# BigClock.net
KiCad netlist of a schematic drawn in EAGLE
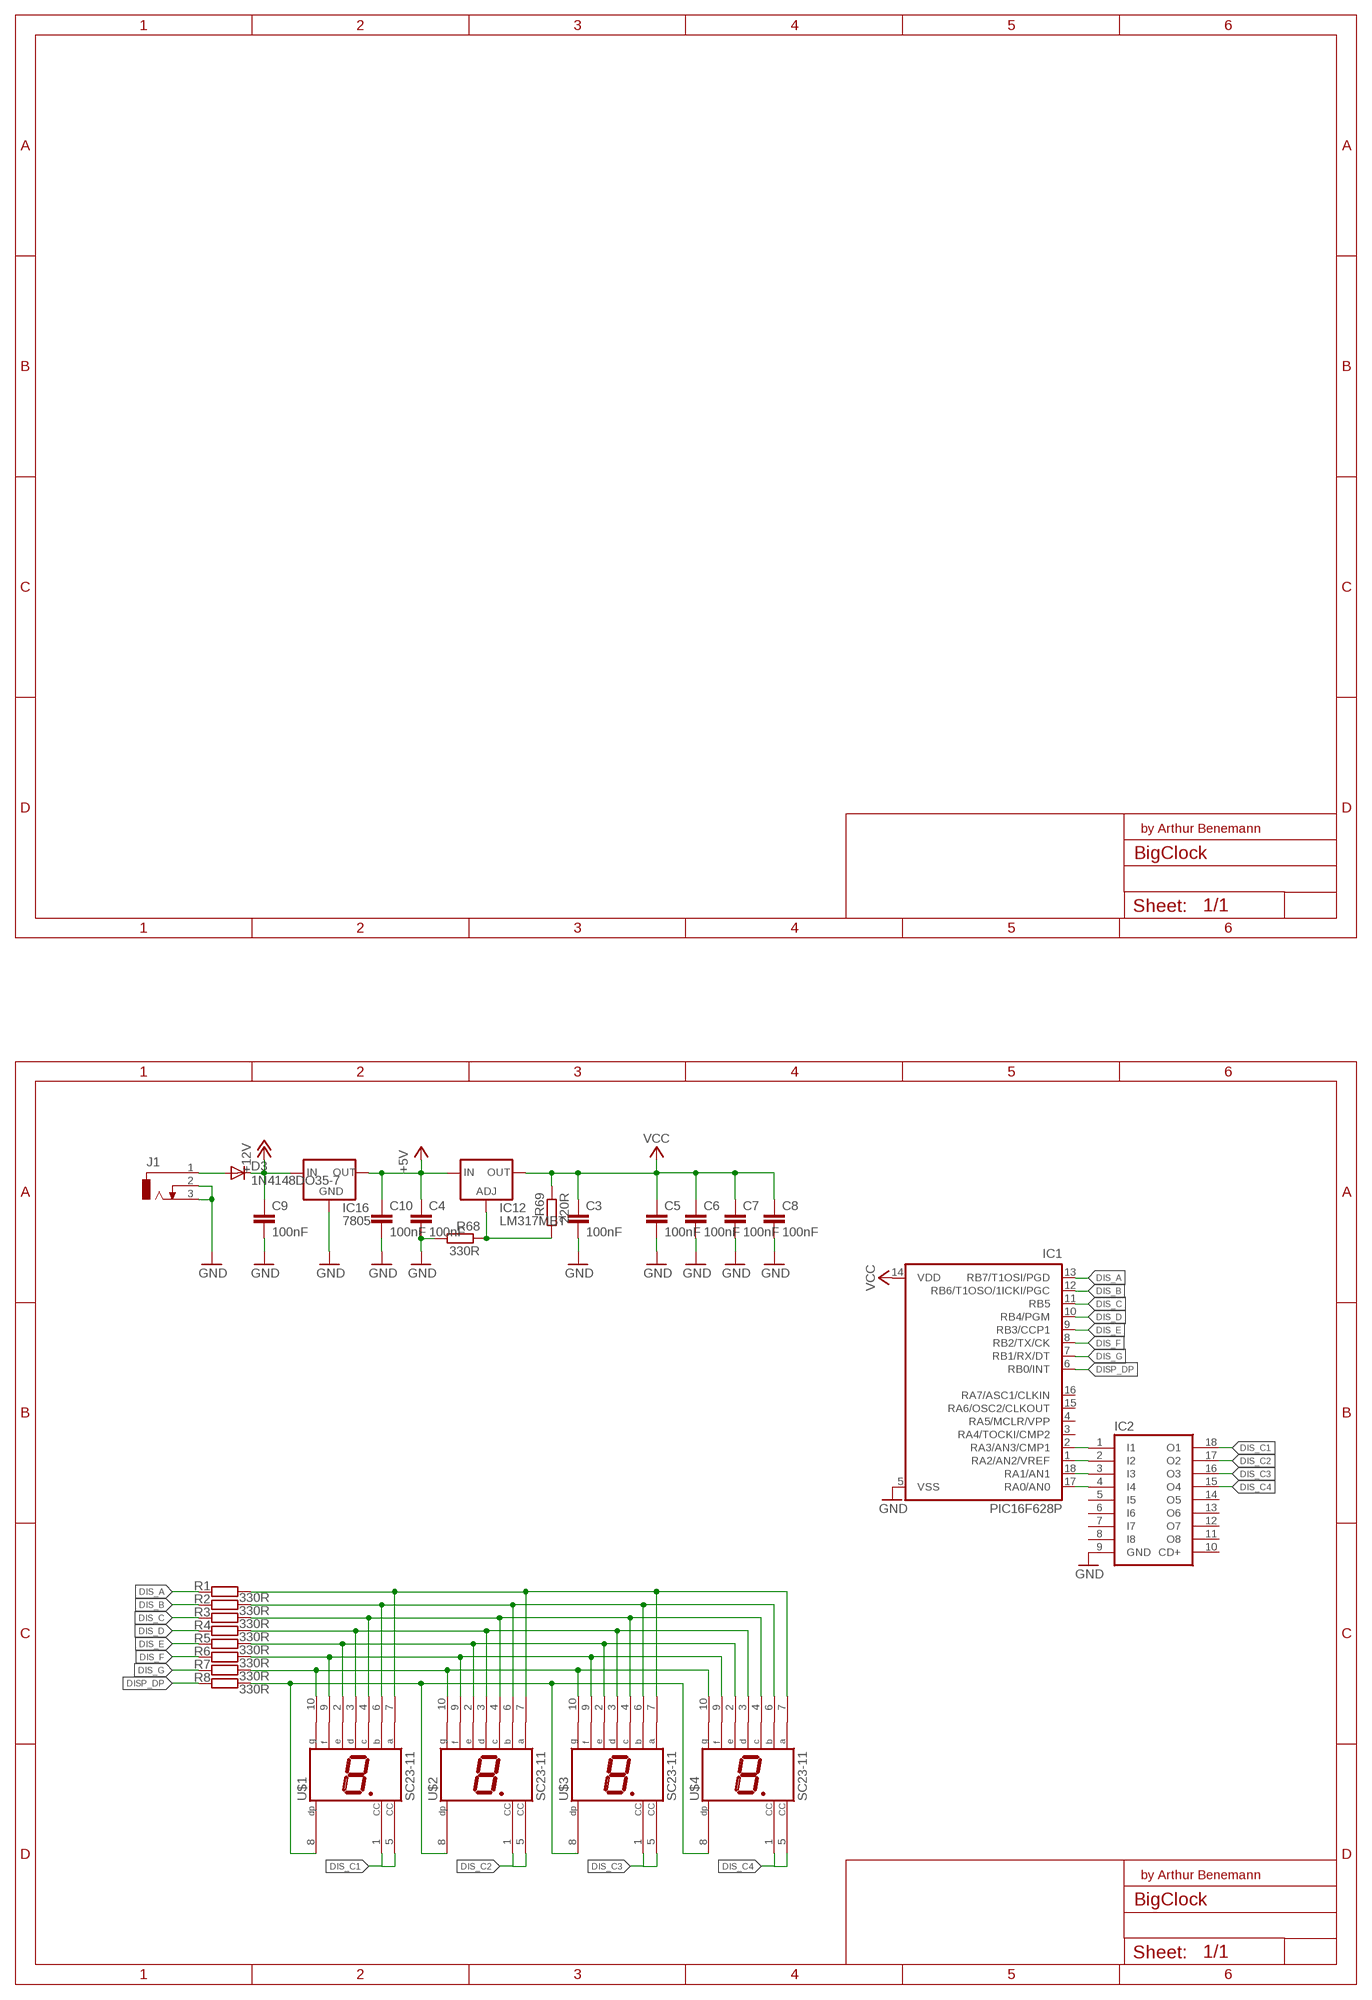
[diagram p0: schematic, sheet 1]

(export (version "E")
  (design (tool "Eeschema 10.0.6"))
  (components
    (comp (ref "C3")
      (value "100nF")
      (footprint "eagle-import:C050-025X075")
      (libsource (lib "eagle-import") (part "C-EU050-025X075"))
    )
    (comp (ref "C4")
      (value "100nF")
      (footprint "eagle-import:C050-025X075")
      (libsource (lib "eagle-import") (part "C-EU050-025X075"))
    )
    (comp (ref "C5")
      (value "100nF")
      (footprint "eagle-import:C050-025X075")
      (libsource (lib "eagle-import") (part "C-EU050-025X075"))
    )
    (comp (ref "C6")
      (value "100nF")
      (footprint "eagle-import:C050-025X075")
      (libsource (lib "eagle-import") (part "C-EU050-025X075"))
    )
    (comp (ref "C7")
      (value "100nF")
      (footprint "eagle-import:C050-025X075")
      (libsource (lib "eagle-import") (part "C-EU050-025X075"))
    )
    (comp (ref "C8")
      (value "100nF")
      (footprint "eagle-import:C050-025X075")
      (libsource (lib "eagle-import") (part "C-EU050-025X075"))
    )
    (comp (ref "C9")
      (value "100nF")
      (footprint "eagle-import:C050-025X075")
      (libsource (lib "eagle-import") (part "C-EU050-025X075"))
    )
    (comp (ref "C10")
      (value "100nF")
      (footprint "eagle-import:C050-025X075")
      (libsource (lib "eagle-import") (part "C-EU050-025X075"))
    )
    (comp (ref "D3")
      (value "1N4148DO35-7")
      (footprint "eagle-import:DO35-7")
      (libsource (lib "eagle-import") (part "1N4148DO35-7"))
    )
    (comp (ref "IC1")
      (value "PIC16F628P")
      (footprint "eagle-import:DIL18")
      (fields (field (name "MF") "MICROCHIP") (field (name "MPN") "PIC16F628-20/P"))
      (libsource (lib "eagle-import") (part "PIC16F628P"))
    )
    (comp (ref "IC2")
      (value "ULN2803A")
      (footprint "eagle-import:DIL18")
      (libsource (lib "eagle-import") (part "ULN2803A"))
    )
    (comp (ref "IC12")
      (value "LM317MBT")
      (footprint "eagle-import:TO220L1")
      (libsource (lib "eagle-import") (part "LM317?MBT"))
    )
    (comp (ref "IC16")
      (value "7805")
      (footprint "eagle-import:78XXL")
      (libsource (lib "eagle-import") (part "78XXL"))
    )
    (comp (ref "J1")
      (value "DCJ0303")
      (footprint "eagle-import:DCJ0303")
      (libsource (lib "eagle-import") (part "DCJ0303"))
    )
    (comp (ref "R1")
      (value "330R")
      (footprint "eagle-import:0204_5")
      (libsource (lib "eagle-import") (part "R-EU_0204/5"))
    )
    (comp (ref "R2")
      (value "330R")
      (footprint "eagle-import:0204_5")
      (libsource (lib "eagle-import") (part "R-EU_0204/5"))
    )
    (comp (ref "R3")
      (value "330R")
      (footprint "eagle-import:0204_5")
      (libsource (lib "eagle-import") (part "R-EU_0204/5"))
    )
    (comp (ref "R4")
      (value "330R")
      (footprint "eagle-import:0204_5")
      (libsource (lib "eagle-import") (part "R-EU_0204/5"))
    )
    (comp (ref "R5")
      (value "330R")
      (footprint "eagle-import:0204_5")
      (libsource (lib "eagle-import") (part "R-EU_0204/5"))
    )
    (comp (ref "R6")
      (value "330R")
      (footprint "eagle-import:0204_5")
      (libsource (lib "eagle-import") (part "R-EU_0204/5"))
    )
    (comp (ref "R7")
      (value "330R")
      (footprint "eagle-import:0204_5")
      (libsource (lib "eagle-import") (part "R-EU_0204/5"))
    )
    (comp (ref "R8")
      (value "330R")
      (footprint "eagle-import:0204_5")
      (libsource (lib "eagle-import") (part "R-EU_0204/5"))
    )
    (comp (ref "R68")
      (value "330R")
      (footprint "eagle-import:0204_5")
      (libsource (lib "eagle-import") (part "R-EU_0204/5"))
    )
    (comp (ref "R69")
      (value "220R")
      (footprint "eagle-import:0204_5")
      (libsource (lib "eagle-import") (part "R-EU_0204/5"))
    )
    (comp (ref "U$1")
      (value "SC23-11")
      (footprint "eagle-import:SX23-XX")
      (libsource (lib "eagle-import") (part "SC23-11"))
    )
    (comp (ref "U$2")
      (value "SC23-11")
      (footprint "eagle-import:SX23-XX")
      (libsource (lib "eagle-import") (part "SC23-11"))
    )
    (comp (ref "U$3")
      (value "SC23-11")
      (footprint "eagle-import:SX23-XX")
      (libsource (lib "eagle-import") (part "SC23-11"))
    )
    (comp (ref "U$4")
      (value "SC23-11")
      (footprint "eagle-import:SX23-XX")
      (libsource (lib "eagle-import") (part "SC23-11"))
    )
  )
  (nets
    (net (code "1") (name "+5V") (class "Default")
      (node (ref "C10") (pin "1") (pinfunction "1_1") (pintype "passive"))
      (node (ref "C4") (pin "1") (pinfunction "1_1") (pintype "passive"))
      (node (ref "IC12") (pin "3") (pinfunction "IN_3") (pintype "input"))
      (node (ref "IC16") (pin "OUT") (pinfunction "OUT_OUT") (pintype "passive"))
    )
    (net (code "2") (name "+12V") (class "Default")
      (node (ref "C9") (pin "1") (pinfunction "1_1") (pintype "passive"))
      (node (ref "D3") (pin "C") (pinfunction "C_C") (pintype "passive"))
      (node (ref "IC16") (pin "IN") (pinfunction "IN_IN") (pintype "input"))
    )
    (net (code "3") (name "DISP_DP") (class "Default")
      (node (ref "IC1") (pin "6") (pinfunction "RB0/INT_6") (pintype "bidirectional"))
      (node (ref "R8") (pin "2") (pinfunction "2_2") (pintype "passive"))
    )
    (net (code "4") (name "DIS_A") (class "Default")
      (node (ref "IC1") (pin "13") (pinfunction "RB7/T1OSI/PGD_13") (pintype "bidirectional"))
      (node (ref "R1") (pin "2") (pinfunction "2_2") (pintype "passive"))
    )
    (net (code "5") (name "DIS_B") (class "Default")
      (node (ref "IC1") (pin "12") (pinfunction "RB6/T1OSO/1ICKI/PGC_12") (pintype "bidirectional"))
      (node (ref "R2") (pin "2") (pinfunction "2_2") (pintype "passive"))
    )
    (net (code "6") (name "DIS_C") (class "Default")
      (node (ref "IC1") (pin "11") (pinfunction "RB5_11") (pintype "bidirectional"))
      (node (ref "R3") (pin "2") (pinfunction "2_2") (pintype "passive"))
    )
    (net (code "7") (name "DIS_C1") (class "Default")
      (node (ref "IC2") (pin "18") (pinfunction "O1_18") (pintype "open_collector"))
      (node (ref "U$1") (pin "1") (pinfunction "CC_1") (pintype "passive"))
      (node (ref "U$1") (pin "5") (pinfunction "CC_5") (pintype "passive"))
    )
    (net (code "8") (name "DIS_C2") (class "Default")
      (node (ref "IC2") (pin "17") (pinfunction "O2_17") (pintype "open_collector"))
      (node (ref "U$2") (pin "1") (pinfunction "CC_1") (pintype "passive"))
      (node (ref "U$2") (pin "5") (pinfunction "CC_5") (pintype "passive"))
    )
    (net (code "9") (name "DIS_C3") (class "Default")
      (node (ref "IC2") (pin "16") (pinfunction "O3_16") (pintype "open_collector"))
      (node (ref "U$3") (pin "1") (pinfunction "CC_1") (pintype "passive"))
      (node (ref "U$3") (pin "5") (pinfunction "CC_5") (pintype "passive"))
    )
    (net (code "10") (name "DIS_C4") (class "Default")
      (node (ref "IC2") (pin "15") (pinfunction "O4_15") (pintype "open_collector"))
      (node (ref "U$4") (pin "1") (pinfunction "CC_1") (pintype "passive"))
      (node (ref "U$4") (pin "5") (pinfunction "CC_5") (pintype "passive"))
    )
    (net (code "11") (name "DIS_D") (class "Default")
      (node (ref "IC1") (pin "10") (pinfunction "RB4/PGM_10") (pintype "bidirectional"))
      (node (ref "R4") (pin "2") (pinfunction "2_2") (pintype "passive"))
    )
    (net (code "12") (name "DIS_E") (class "Default")
      (node (ref "IC1") (pin "9") (pinfunction "RB3/CCP1_9") (pintype "bidirectional"))
      (node (ref "R5") (pin "2") (pinfunction "2_2") (pintype "passive"))
    )
    (net (code "13") (name "DIS_F") (class "Default")
      (node (ref "IC1") (pin "8") (pinfunction "RB2/TX/CK_8") (pintype "bidirectional"))
      (node (ref "R6") (pin "2") (pinfunction "2_2") (pintype "passive"))
    )
    (net (code "14") (name "DIS_G") (class "Default")
      (node (ref "IC1") (pin "7") (pinfunction "RB1/RX/DT_7") (pintype "bidirectional"))
      (node (ref "R7") (pin "2") (pinfunction "2_2") (pintype "passive"))
    )
    (net (code "15") (name "GND") (class "Default")
      (node (ref "C10") (pin "2") (pinfunction "2_2") (pintype "passive"))
      (node (ref "C3") (pin "2") (pinfunction "2_2") (pintype "passive"))
      (node (ref "C4") (pin "2") (pinfunction "2_2") (pintype "passive"))
      (node (ref "C5") (pin "2") (pinfunction "2_2") (pintype "passive"))
      (node (ref "C6") (pin "2") (pinfunction "2_2") (pintype "passive"))
      (node (ref "C7") (pin "2") (pinfunction "2_2") (pintype "passive"))
      (node (ref "C8") (pin "2") (pinfunction "2_2") (pintype "passive"))
      (node (ref "C9") (pin "2") (pinfunction "2_2") (pintype "passive"))
      (node (ref "IC1") (pin "5") (pinfunction "VSS_5") (pintype "power_in"))
      (node (ref "IC16") (pin "GND") (pinfunction "GND_GND") (pintype "input"))
      (node (ref "IC2") (pin "9") (pinfunction "GND_9") (pintype "power_in"))
      (node (ref "J1") (pin "2") (pinfunction "2_2") (pintype "passive"))
      (node (ref "J1") (pin "3") (pinfunction "3_3") (pintype "passive"))
      (node (ref "R68") (pin "2") (pinfunction "2_2") (pintype "passive"))
    )
    (net (code "16") (name "Net-(D3-PadA)") (class "Default")
      (node (ref "D3") (pin "A") (pinfunction "A_A") (pintype "passive"))
      (node (ref "J1") (pin "1") (pinfunction "1_1") (pintype "passive"))
    )
    (net (code "17") (name "Net-(IC1-RA0{slash}AN0)") (class "Default")
      (node (ref "IC1") (pin "17") (pinfunction "RA0/AN0_17") (pintype "bidirectional"))
      (node (ref "IC2") (pin "4") (pinfunction "I4_4") (pintype "input"))
    )
    (net (code "18") (name "Net-(IC1-RA1{slash}AN1)") (class "Default")
      (node (ref "IC1") (pin "18") (pinfunction "RA1/AN1_18") (pintype "bidirectional"))
      (node (ref "IC2") (pin "3") (pinfunction "I3_3") (pintype "input"))
    )
    (net (code "19") (name "Net-(IC1-RA2{slash}AN2{slash}VREF)") (class "Default")
      (node (ref "IC1") (pin "1") (pinfunction "RA2/AN2/VREF_1") (pintype "bidirectional"))
      (node (ref "IC2") (pin "2") (pinfunction "I2_2") (pintype "input"))
    )
    (net (code "20") (name "Net-(IC1-RA3{slash}AN3{slash}CMP1)") (class "Default")
      (node (ref "IC1") (pin "2") (pinfunction "RA3/AN3/CMP1_2") (pintype "bidirectional"))
      (node (ref "IC2") (pin "1") (pinfunction "I1_1") (pintype "input"))
    )
    (net (code "21") (name "Net-(IC12-ADJ)") (class "Default")
      (node (ref "IC12") (pin "1") (pinfunction "ADJ_1") (pintype "input"))
      (node (ref "R68") (pin "1") (pinfunction "1_1") (pintype "passive"))
      (node (ref "R69") (pin "2") (pinfunction "2_2") (pintype "passive"))
    )
    (net (code "22") (name "Net-(U$1-A)") (class "Default")
      (node (ref "R1") (pin "1") (pinfunction "1_1") (pintype "passive"))
      (node (ref "U$1") (pin "7") (pinfunction "A_7") (pintype "passive"))
      (node (ref "U$2") (pin "7") (pinfunction "A_7") (pintype "passive"))
      (node (ref "U$3") (pin "7") (pinfunction "A_7") (pintype "passive"))
      (node (ref "U$4") (pin "7") (pinfunction "A_7") (pintype "passive"))
    )
    (net (code "23") (name "Net-(U$1-B)") (class "Default")
      (node (ref "R2") (pin "1") (pinfunction "1_1") (pintype "passive"))
      (node (ref "U$1") (pin "6") (pinfunction "B_6") (pintype "passive"))
      (node (ref "U$2") (pin "6") (pinfunction "B_6") (pintype "passive"))
      (node (ref "U$3") (pin "6") (pinfunction "B_6") (pintype "passive"))
      (node (ref "U$4") (pin "6") (pinfunction "B_6") (pintype "passive"))
    )
    (net (code "24") (name "Net-(U$1-C)") (class "Default")
      (node (ref "R3") (pin "1") (pinfunction "1_1") (pintype "passive"))
      (node (ref "U$1") (pin "4") (pinfunction "C_4") (pintype "passive"))
      (node (ref "U$2") (pin "4") (pinfunction "C_4") (pintype "passive"))
      (node (ref "U$3") (pin "4") (pinfunction "C_4") (pintype "passive"))
      (node (ref "U$4") (pin "4") (pinfunction "C_4") (pintype "passive"))
    )
    (net (code "25") (name "Net-(U$1-D)") (class "Default")
      (node (ref "R4") (pin "1") (pinfunction "1_1") (pintype "passive"))
      (node (ref "U$1") (pin "3") (pinfunction "D_3") (pintype "passive"))
      (node (ref "U$2") (pin "3") (pinfunction "D_3") (pintype "passive"))
      (node (ref "U$3") (pin "3") (pinfunction "D_3") (pintype "passive"))
      (node (ref "U$4") (pin "3") (pinfunction "D_3") (pintype "passive"))
    )
    (net (code "26") (name "Net-(U$1-DP)") (class "Default")
      (node (ref "R8") (pin "1") (pinfunction "1_1") (pintype "passive"))
      (node (ref "U$1") (pin "8") (pinfunction "DP_8") (pintype "passive"))
      (node (ref "U$2") (pin "8") (pinfunction "DP_8") (pintype "passive"))
      (node (ref "U$3") (pin "8") (pinfunction "DP_8") (pintype "passive"))
      (node (ref "U$4") (pin "8") (pinfunction "DP_8") (pintype "passive"))
    )
    (net (code "27") (name "Net-(U$1-E)") (class "Default")
      (node (ref "R5") (pin "1") (pinfunction "1_1") (pintype "passive"))
      (node (ref "U$1") (pin "2") (pinfunction "E_2") (pintype "passive"))
      (node (ref "U$2") (pin "2") (pinfunction "E_2") (pintype "passive"))
      (node (ref "U$3") (pin "2") (pinfunction "E_2") (pintype "passive"))
      (node (ref "U$4") (pin "2") (pinfunction "E_2") (pintype "passive"))
    )
    (net (code "28") (name "Net-(U$1-F)") (class "Default")
      (node (ref "R6") (pin "1") (pinfunction "1_1") (pintype "passive"))
      (node (ref "U$1") (pin "9") (pinfunction "F_9") (pintype "passive"))
      (node (ref "U$2") (pin "9") (pinfunction "F_9") (pintype "passive"))
      (node (ref "U$3") (pin "9") (pinfunction "F_9") (pintype "passive"))
      (node (ref "U$4") (pin "9") (pinfunction "F_9") (pintype "passive"))
    )
    (net (code "29") (name "Net-(U$1-G)") (class "Default")
      (node (ref "R7") (pin "1") (pinfunction "1_1") (pintype "passive"))
      (node (ref "U$1") (pin "10") (pinfunction "G_10") (pintype "passive"))
      (node (ref "U$2") (pin "10") (pinfunction "G_10") (pintype "passive"))
      (node (ref "U$3") (pin "10") (pinfunction "G_10") (pintype "passive"))
      (node (ref "U$4") (pin "10") (pinfunction "G_10") (pintype "passive"))
    )
    (net (code "30") (name "VCC") (class "Default")
      (node (ref "C3") (pin "1") (pinfunction "1_1") (pintype "passive"))
      (node (ref "C5") (pin "1") (pinfunction "1_1") (pintype "passive"))
      (node (ref "C6") (pin "1") (pinfunction "1_1") (pintype "passive"))
      (node (ref "C7") (pin "1") (pinfunction "1_1") (pintype "passive"))
      (node (ref "C8") (pin "1") (pinfunction "1_1") (pintype "passive"))
      (node (ref "IC1") (pin "14") (pinfunction "VDD_14") (pintype "power_in"))
      (node (ref "IC12") (pin "2") (pinfunction "OUT_2") (pintype "passive"))
      (node (ref "R69") (pin "1") (pinfunction "1_1") (pintype "passive"))
    )
    (net (code "31") (name "unconnected-(IC1-RA4{slash}TOCKI{slash}CMP2-Pad3)") (class "Default")
      (node (ref "IC1") (pin "3") (pinfunction "RA4/TOCKI/CMP2_3") (pintype "bidirectional"))
    )
    (net (code "32") (name "unconnected-(IC1-RA5{slash}MCLR{slash}VPP-Pad4)") (class "Default")
      (node (ref "IC1") (pin "4") (pinfunction "RA5/MCLR/VPP_4") (pintype "input"))
    )
    (net (code "33") (name "unconnected-(IC1-RA6{slash}OSC2{slash}CLKOUT-Pad15)") (class "Default")
      (node (ref "IC1") (pin "15") (pinfunction "RA6/OSC2/CLKOUT_15") (pintype "bidirectional"))
    )
    (net (code "34") (name "unconnected-(IC1-RA7{slash}ASC1{slash}CLKIN-Pad16)") (class "Default")
      (node (ref "IC1") (pin "16") (pinfunction "RA7/ASC1/CLKIN_16") (pintype "bidirectional"))
    )
    (net (code "35") (name "unconnected-(IC2-CD+-Pad10)") (class "Default")
      (node (ref "IC2") (pin "10") (pinfunction "CD+_10") (pintype "passive"))
    )
    (net (code "36") (name "unconnected-(IC2-I5-Pad5)") (class "Default")
      (node (ref "IC2") (pin "5") (pinfunction "I5_5") (pintype "input"))
    )
    (net (code "37") (name "unconnected-(IC2-I6-Pad6)") (class "Default")
      (node (ref "IC2") (pin "6") (pinfunction "I6_6") (pintype "input"))
    )
    (net (code "38") (name "unconnected-(IC2-I7-Pad7)") (class "Default")
      (node (ref "IC2") (pin "7") (pinfunction "I7_7") (pintype "input"))
    )
    (net (code "39") (name "unconnected-(IC2-I8-Pad8)") (class "Default")
      (node (ref "IC2") (pin "8") (pinfunction "I8_8") (pintype "input"))
    )
    (net (code "40") (name "unconnected-(IC2-O5-Pad14)") (class "Default")
      (node (ref "IC2") (pin "14") (pinfunction "O5_14") (pintype "open_collector"))
    )
    (net (code "41") (name "unconnected-(IC2-O6-Pad13)") (class "Default")
      (node (ref "IC2") (pin "13") (pinfunction "O6_13") (pintype "open_collector"))
    )
    (net (code "42") (name "unconnected-(IC2-O7-Pad12)") (class "Default")
      (node (ref "IC2") (pin "12") (pinfunction "O7_12") (pintype "open_collector"))
    )
    (net (code "43") (name "unconnected-(IC2-O8-Pad11)") (class "Default")
      (node (ref "IC2") (pin "11") (pinfunction "O8_11") (pintype "open_collector"))
    )
  )
)
